# Sch_mcu_brd_external_connectors.net
KiCad netlist of a schematic drawn in Altium Designer
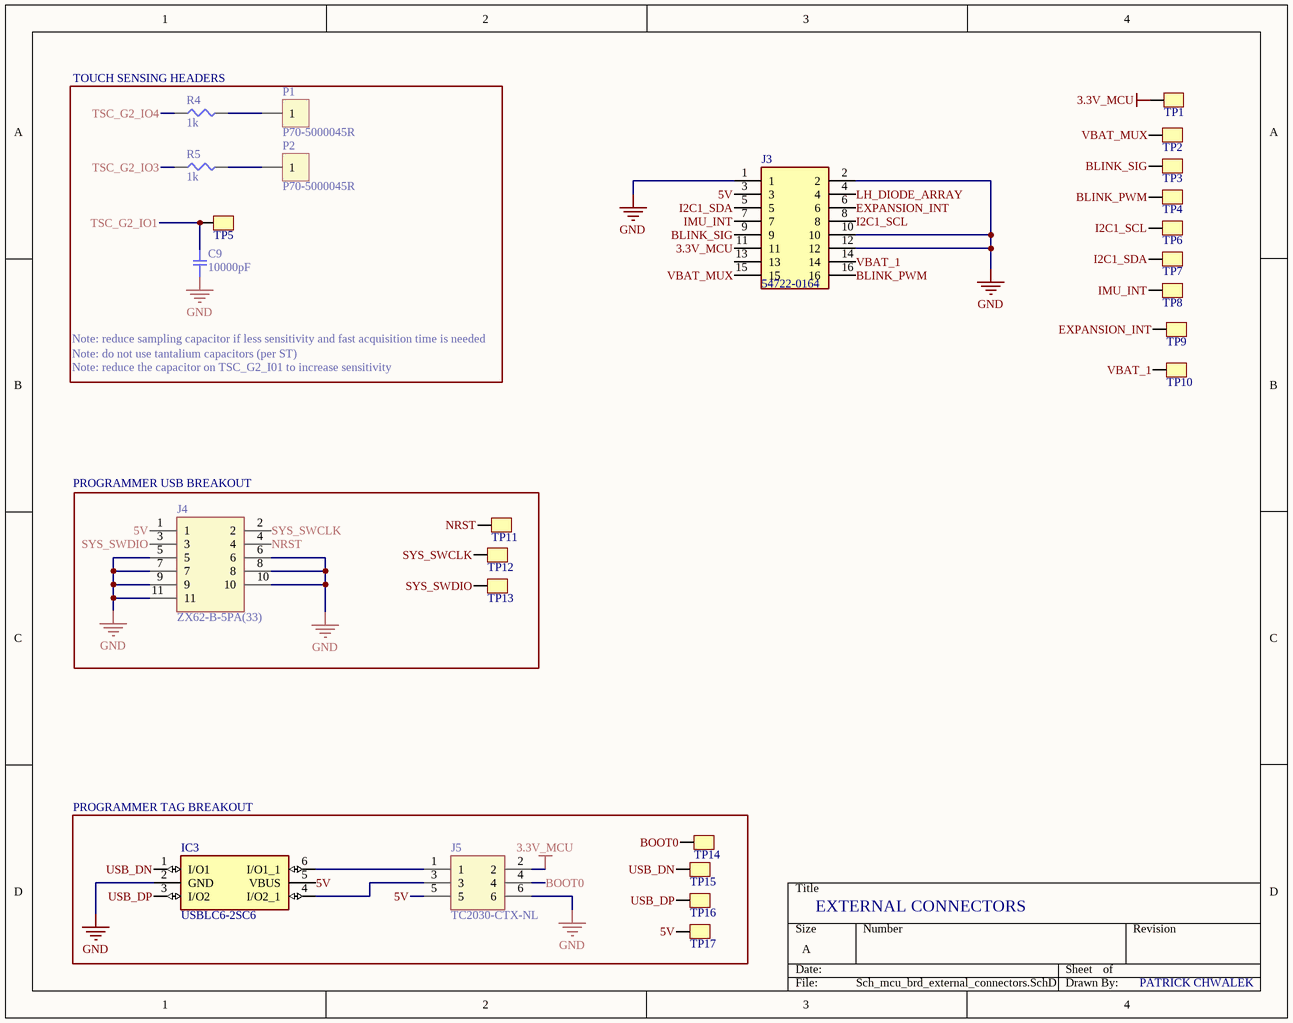
[diagram p0: Sch_mcu_brd_external_connectors.SchDoc]

(export (version "E")
  (design (tool "Eeschema 10.0.6"))
  (components
    (comp (ref "C9")
      (value "10000pF")
      (footprint "SMD-0402C")
      (description "CAP CER 10000PF 50V X7R 0402")
      (fields
        (field (name "DIGI-KEY PART NUMBER") "490-4762-1-ND")
        (field (name "PART NUMBER") "GCM155R71H103KA55D")
      )
      (libsource (lib "capacitor_murata_0402") (part "GCM155R71H103KA55D"))
    )
    (comp (ref "IC3")
      (value "USBLC6-2SC6")
      (footprint "SamacSys:SOT95P280X145-6N")
      (description "Integrated Circuit")
      (fields (field (name "MOUSER PART NUMBER") "511-USBLC6-2SC6") (field (name "RS PART NUMBER") "9206266"))
      (libsource (lib "SamacSys") (part "USBLC6-2SC6"))
    )
    (comp (ref "J3")
      (value "54722-0164")
      (footprint "SamacSys:54722-0164")
      (description "Connector")
      (fields (field (name "MOUSER PART NUMBER") "538-54722-0164") (field (name "RS PART NUMBER") "7206511"))
      (libsource (lib "SamacSys") (part "54722-0164"))
    )
    (comp (ref "J4")
      (value "ZX62-B-5PA(33)")
      (footprint "SamacSys:ZX62B5PA33")
      (description "Connector")
      (fields
        (field (name "MOUSER PART NUMBER") "798-ZX62-B-5PA33")
        (field (name "RS PART NUMBER") "1362267")
      )
      (libsource (lib "SamacSys") (part "ZX62-B-5PA(33)"))
    )
    (comp (ref "J5")
      (value "TC2030-CTX-NL")
      (footprint "SamacSys:TC2030MCPNL10")
      (description "Connector")
      (libsource (lib "SamacSys") (part "TC2030-CTX-NL"))
    )
    (comp (ref "P1")
      (value "P70-5000045R")
      (footprint "P70-5000045R")
      (libsource (lib "schematic_components") (part "P70-5000045R"))
    )
    (comp (ref "P2")
      (value "P70-5000045R")
      (footprint "P70-5000045R")
      (libsource (lib "schematic_components") (part "P70-5000045R"))
    )
    (comp (ref "R4")
      (value "1k")
      (footprint "SMD-0402-RES")
      (description "RES SMD 1K OHM 5% 1/10W 0402")
      (fields (field (name "PART NUMBER") "ERJ-2GEJ102X") (field (name "DIGI-KEY PART NUMBER") "P1.0KJCT-ND"))
      (libsource (lib "Panasonic_ERJ_0402") (part "ERJ-2GEJ102X"))
    )
    (comp (ref "R5")
      (value "1k")
      (footprint "SMD-0402-RES")
      (description "RES SMD 1K OHM 5% 1/10W 0402")
      (fields (field (name "PART NUMBER") "ERJ-2GEJ102X") (field (name "DIGI-KEY PART NUMBER") "P1.0KJCT-ND"))
      (libsource (lib "Panasonic_ERJ_0402") (part "ERJ-2GEJ102X"))
    )
    (comp (ref "TP1")
      (value "TestPoint")
      (footprint "TestPoint_0.4mm")
      (libsource (lib "schematic_components") (part "TestPoint"))
    )
    (comp (ref "TP2")
      (value "TestPoint")
      (footprint "TestPoint_0.4mm")
      (libsource (lib "schematic_components") (part "TestPoint"))
    )
    (comp (ref "TP3")
      (value "TestPoint")
      (footprint "TestPoint_0.4mm")
      (libsource (lib "schematic_components") (part "TestPoint"))
    )
    (comp (ref "TP4")
      (value "TestPoint")
      (footprint "TestPoint_0.4mm")
      (libsource (lib "schematic_components") (part "TestPoint"))
    )
    (comp (ref "TP5")
      (value "TestPoint")
      (footprint "TestPoint_0.4mm")
      (libsource (lib "schematic_components") (part "TestPoint"))
    )
    (comp (ref "TP6")
      (value "TestPoint")
      (footprint "TestPoint_0.4mm")
      (libsource (lib "schematic_components") (part "TestPoint"))
    )
    (comp (ref "TP7")
      (value "TestPoint")
      (footprint "TestPoint_0.4mm")
      (libsource (lib "schematic_components") (part "TestPoint"))
    )
    (comp (ref "TP8")
      (value "TestPoint")
      (footprint "TestPoint_0.4mm")
      (libsource (lib "schematic_components") (part "TestPoint"))
    )
    (comp (ref "TP9")
      (value "TestPoint")
      (footprint "TestPoint_0.4mm")
      (libsource (lib "schematic_components") (part "TestPoint"))
    )
    (comp (ref "TP10")
      (value "TestPoint")
      (footprint "TestPoint_0.4mm")
      (libsource (lib "schematic_components") (part "TestPoint"))
    )
    (comp (ref "TP11")
      (value "TestPoint")
      (footprint "TestPoint_0.4mm")
      (libsource (lib "schematic_components") (part "TestPoint"))
    )
    (comp (ref "TP12")
      (value "TestPoint")
      (footprint "TestPoint_0.4mm")
      (libsource (lib "schematic_components") (part "TestPoint"))
    )
    (comp (ref "TP13")
      (value "TestPoint")
      (footprint "TestPoint_0.4mm")
      (libsource (lib "schematic_components") (part "TestPoint"))
    )
    (comp (ref "TP14")
      (value "TestPoint")
      (footprint "TestPoint_0.4mm")
      (libsource (lib "schematic_components") (part "TestPoint"))
    )
    (comp (ref "TP15")
      (value "TestPoint")
      (footprint "TestPoint_0.4mm")
      (libsource (lib "schematic_components") (part "TestPoint"))
    )
    (comp (ref "TP16")
      (value "TestPoint")
      (footprint "TestPoint_0.4mm")
      (libsource (lib "schematic_components") (part "TestPoint"))
    )
    (comp (ref "TP17")
      (value "TestPoint")
      (footprint "TestPoint_0.4mm")
      (libsource (lib "schematic_components") (part "TestPoint"))
    )
  )
  (nets
    (net (code "1") (name "/5V") (class "Default")
      (node (ref "IC3") (pin "5") (pinfunction "VBUS_5") (pintype "passive"))
      (node (ref "J3") (pin "3") (pinfunction "3_3") (pintype "passive"))
      (node (ref "J4") (pin "1") (pinfunction "1_1") (pintype "passive"))
      (node (ref "J5") (pin "5") (pinfunction "5_5") (pintype "passive"))
      (node (ref "TP17") (pin "1") (pinfunction "1_1") (pintype "passive"))
    )
    (net (code "2") (name "/BLINK_PWM") (class "Default")
      (node (ref "J3") (pin "16") (pinfunction "16_16") (pintype "passive"))
      (node (ref "TP4") (pin "1") (pinfunction "1_1") (pintype "passive"))
    )
    (net (code "3") (name "/BLINK_SIG") (class "Default")
      (node (ref "J3") (pin "9") (pinfunction "9_9") (pintype "passive"))
      (node (ref "TP3") (pin "1") (pinfunction "1_1") (pintype "passive"))
    )
    (net (code "4") (name "/BOOT0") (class "Default")
      (node (ref "J5") (pin "4") (pinfunction "4_4") (pintype "passive"))
      (node (ref "TP14") (pin "1") (pinfunction "1_1") (pintype "passive"))
    )
    (net (code "5") (name "/EXPANSION_INT") (class "Default")
      (node (ref "J3") (pin "6") (pinfunction "6_6") (pintype "passive"))
      (node (ref "TP9") (pin "1") (pinfunction "1_1") (pintype "passive"))
    )
    (net (code "6") (name "/I2C1_SCL") (class "Default")
      (node (ref "J3") (pin "8") (pinfunction "8_8") (pintype "passive"))
      (node (ref "TP6") (pin "1") (pinfunction "1_1") (pintype "passive"))
    )
    (net (code "7") (name "/I2C1_SDA") (class "Default")
      (node (ref "J3") (pin "5") (pinfunction "5_5") (pintype "passive"))
      (node (ref "TP7") (pin "1") (pinfunction "1_1") (pintype "passive"))
    )
    (net (code "8") (name "/IMU_INT") (class "Default")
      (node (ref "J3") (pin "7") (pinfunction "7_7") (pintype "passive"))
      (node (ref "TP8") (pin "1") (pinfunction "1_1") (pintype "passive"))
    )
    (net (code "9") (name "/LH_DIODE_ARRAY") (class "Default")
      (node (ref "J3") (pin "4") (pinfunction "4_4") (pintype "passive"))
    )
    (net (code "10") (name "/NRST") (class "Default")
      (node (ref "J4") (pin "4") (pinfunction "4_4") (pintype "passive"))
      (node (ref "TP11") (pin "1") (pinfunction "1_1") (pintype "passive"))
    )
    (net (code "11") (name "/SYS_SWCLK") (class "Default")
      (node (ref "J4") (pin "2") (pinfunction "2_2") (pintype "passive"))
      (node (ref "TP12") (pin "1") (pinfunction "1_1") (pintype "passive"))
    )
    (net (code "12") (name "/SYS_SWDIO") (class "Default")
      (node (ref "J4") (pin "3") (pinfunction "3_3") (pintype "passive"))
      (node (ref "TP13") (pin "1") (pinfunction "1_1") (pintype "passive"))
    )
    (net (code "13") (name "/TSC_G2_IO1") (class "Default")
      (node (ref "C9") (pin "2") (pinfunction "2_2") (pintype "passive"))
      (node (ref "TP5") (pin "1") (pinfunction "1_1") (pintype "passive"))
    )
    (net (code "14") (name "/TSC_G2_IO3") (class "Default")
      (node (ref "R5") (pin "1") (pinfunction "1_1") (pintype "passive"))
    )
    (net (code "15") (name "/TSC_G2_IO4") (class "Default")
      (node (ref "R4") (pin "1") (pinfunction "1_1") (pintype "passive"))
    )
    (net (code "16") (name "/USB_DN") (class "Default")
      (node (ref "IC3") (pin "1") (pinfunction "I/O1_1") (pintype "bidirectional"))
      (node (ref "TP15") (pin "1") (pinfunction "1_1") (pintype "passive"))
    )
    (net (code "17") (name "/USB_DP") (class "Default")
      (node (ref "IC3") (pin "3") (pinfunction "I/O2_3") (pintype "bidirectional"))
      (node (ref "TP16") (pin "1") (pinfunction "1_1") (pintype "passive"))
    )
    (net (code "18") (name "/VBAT_1") (class "Default")
      (node (ref "J3") (pin "14") (pinfunction "14_14") (pintype "passive"))
      (node (ref "TP10") (pin "1") (pinfunction "1_1") (pintype "passive"))
    )
    (net (code "19") (name "/VBAT_MUX") (class "Default")
      (node (ref "J3") (pin "15") (pinfunction "15_15") (pintype "passive"))
      (node (ref "TP2") (pin "1") (pinfunction "1_1") (pintype "passive"))
    )
    (net (code "20") (name "3.3V_MCU") (class "Default")
      (node (ref "J3") (pin "11") (pinfunction "11_11") (pintype "passive"))
      (node (ref "J5") (pin "2") (pinfunction "2_2") (pintype "passive"))
      (node (ref "TP1") (pin "1") (pinfunction "1_1") (pintype "passive"))
    )
    (net (code "21") (name "GND") (class "Default")
      (node (ref "C9") (pin "1") (pinfunction "1_1") (pintype "passive"))
      (node (ref "IC3") (pin "2") (pinfunction "GND_2") (pintype "power_in"))
      (node (ref "J3") (pin "1") (pinfunction "1_1") (pintype "passive"))
      (node (ref "J3") (pin "10") (pinfunction "10_10") (pintype "passive"))
      (node (ref "J3") (pin "12") (pinfunction "12_12") (pintype "passive"))
      (node (ref "J3") (pin "2") (pinfunction "2_2") (pintype "passive"))
      (node (ref "J4") (pin "10") (pinfunction "10_10") (pintype "passive"))
      (node (ref "J4") (pin "11") (pinfunction "11_11") (pintype "passive"))
      (node (ref "J4") (pin "5") (pinfunction "5_5") (pintype "passive"))
      (node (ref "J4") (pin "6") (pinfunction "6_6") (pintype "passive"))
      (node (ref "J4") (pin "7") (pinfunction "7_7") (pintype "passive"))
      (node (ref "J4") (pin "8") (pinfunction "8_8") (pintype "passive"))
      (node (ref "J4") (pin "9") (pinfunction "9_9") (pintype "passive"))
      (node (ref "J5") (pin "6") (pinfunction "6_6") (pintype "passive"))
    )
    (net (code "22") (name "Net-(IC3-I{slash}O1_1)") (class "Default")
      (node (ref "IC3") (pin "6") (pinfunction "I/O1_1_6") (pintype "bidirectional"))
      (node (ref "J5") (pin "1") (pinfunction "1_1") (pintype "passive"))
    )
    (net (code "23") (name "Net-(IC3-I{slash}O2_1)") (class "Default")
      (node (ref "IC3") (pin "4") (pinfunction "I/O2_1_4") (pintype "bidirectional"))
      (node (ref "J5") (pin "3") (pinfunction "3_3") (pintype "passive"))
    )
    (net (code "24") (name "Net-(P1-Pad1)") (class "Default")
      (node (ref "P1") (pin "1") (pinfunction "1_1") (pintype "passive"))
      (node (ref "R4") (pin "2") (pinfunction "2_2") (pintype "passive"))
    )
    (net (code "25") (name "Net-(P2-Pad1)") (class "Default")
      (node (ref "P2") (pin "1") (pinfunction "1_1") (pintype "passive"))
      (node (ref "R5") (pin "2") (pinfunction "2_2") (pintype "passive"))
    )
    (net (code "26") (name "unconnected-(J3-Pad13)") (class "Default")
      (node (ref "J3") (pin "13") (pinfunction "13_13") (pintype "passive"))
    )
  )
)
